# USB_UART.net
KiCad netlist of a schematic drawn in Altium Designer
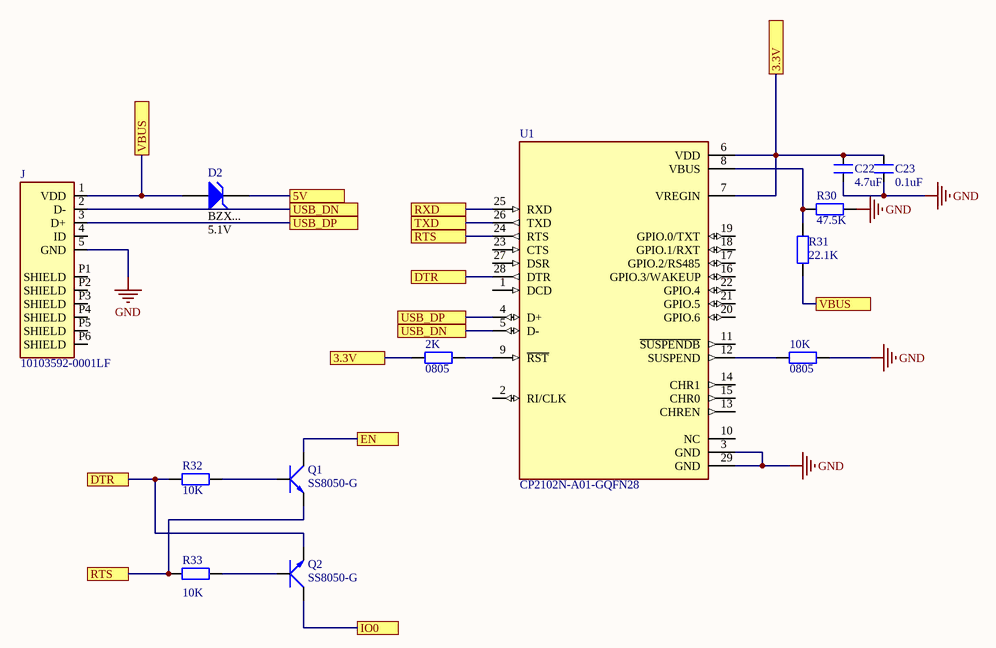
[diagram p0: USB_UART.SchDoc]

(export (version "E")
  (design (tool "Eeschema 10.0.6"))
  (components
    (comp (ref "2K")
      (value "0805")
      (footprint "DIEN TRO 0805")
      (description "RES_0805")
      (fields (field (name "Comment") "RES_SMD_0805") (field (name "PUBLISHER") "Altium Limited"))
      (libsource (lib "") (part "RES_SMD_0805_1"))
    )
    (comp (ref "10K")
      (value "0805")
      (footprint "DIEN TRO 0805")
      (description "RES_0805")
      (fields (field (name "Comment") "RES_SMD_0805") (field (name "PUBLISHER") "Altium Limited"))
      (libsource (lib "") (part "RES_SMD_0805_1"))
    )
    (comp (ref "C22")
      (value "4.7uF")
      (footprint "SM-0805")
      (description "Cap SMD")
      (libsource (lib "hphonglib") (part "CM"))
    )
    (comp (ref "C23")
      (value "0.1uF")
      (footprint "SM-0805")
      (description "Cap SMD")
      (libsource (lib "hphonglib") (part "CM"))
    )
    (comp (ref "D2")
      (value "BZX...")
      (footprint "D1208")
      (description "Zener Diode")
      (fields
        (field (name "VOLT") "5.1V")
        (field (name "Comment") "Diode Zener")
        (field (name "PUBLISHER") "Altium Limited")
      )
      (libsource (lib "hphonglib") (part "Diode Zener"))
    )
    (comp (ref "J")
      (value "10103592-0001LF")
      (footprint "AMPHENOL_10103592-0001LF")
      (description "USB - micro B USB 2.0 Receptacle Connector 5 Position Surface Mount, Right Angle; Through Hole")
      (fields (field (name "MF") "Amphenol ICC"))
      (libsource (lib "EMG_IoT_V2.0") (part "10103592-0001LF"))
    )
    (comp (ref "Q1")
      (value "SS8050-G")
      (footprint "SOT23B")
      (description "NPN 600mW, ECB")
      (libsource (lib "hphonglib") (part "C1815_1"))
    )
    (comp (ref "Q2")
      (value "SS8050-G")
      (footprint "SOT23B")
      (description "NPN 600mW, ECB")
      (libsource (lib "hphonglib") (part "C1815_1"))
    )
    (comp (ref "R30")
      (value "47.5K")
      (footprint "DIEN TRO 0805")
      (description "RES_0805")
      (fields (field (name "Comment") "RES_SMD_0805") (field (name "PUBLISHER") "Altium Limited"))
      (libsource (lib "") (part "RES_SMD_0805_1"))
    )
    (comp (ref "R31")
      (value "22.1K")
      (footprint "DIEN TRO 0805")
      (description "RES_0805")
      (fields (field (name "Comment") "RES_SMD_0805") (field (name "PUBLISHER") "Altium Limited"))
      (libsource (lib "hphonglib") (part "RES_SMD_0805"))
    )
    (comp (ref "R32")
      (value "10K")
      (footprint "DIEN TRO 0805")
      (description "RES_0805")
      (fields (field (name "Comment") "RES_SMD_0805") (field (name "PUBLISHER") "Altium Limited"))
      (libsource (lib "") (part "RES_SMD_0805_1"))
    )
    (comp (ref "R33")
      (value "10K")
      (footprint "DIEN TRO 0805")
      (description "RES_0805")
      (fields (field (name "Comment") "RES_SMD_0805") (field (name "PUBLISHER") "Altium Limited"))
      (libsource (lib "") (part "RES_SMD_0805_1"))
    )
    (comp (ref "U1")
      (value "CP2102N-A01-GQFN28")
      (footprint "QFN50P500X500X80-29N")
      (description "USB Bridge, USB to UART USB 2.0 UART Interface 28-QFN (5x5)")
      (fields (field (name "MF") "Silicon Labs"))
      (libsource (lib "EMG_IoT_V2.0") (part "CP2102N-A01-GQFN28"))
    )
  )
  (nets
    (net (code "1") (name "/3.3V") (class "Default")
      (node (ref "2K") (pin "1") (pinfunction "1_1") (pintype "passive"))
      (node (ref "C22") (pin "2") (pinfunction "2_2") (pintype "passive"))
      (node (ref "C23") (pin "2") (pinfunction "2_2") (pintype "passive"))
      (node (ref "U1") (pin "6") (pinfunction "VDD_6") (pintype "power_in"))
      (node (ref "U1") (pin "7") (pinfunction "VREGIN_7") (pintype "power_in"))
    )
    (net (code "2") (name "/5V") (class "Default")
      (node (ref "D2") (pin "2") (pinfunction "K_2") (pintype "passive"))
    )
    (net (code "3") (name "/DTR") (class "Default")
      (node (ref "Q2") (pin "1") (pinfunction "E_1") (pintype "passive"))
      (node (ref "R32") (pin "1") (pinfunction "1_1") (pintype "passive"))
      (node (ref "U1") (pin "28") (pinfunction "DTR_28") (pintype "output"))
    )
    (net (code "4") (name "/EN") (class "Default")
      (node (ref "Q1") (pin "2") (pinfunction "C_2") (pintype "passive"))
    )
    (net (code "5") (name "/IO0") (class "Default")
      (node (ref "Q2") (pin "2") (pinfunction "C_2") (pintype "passive"))
    )
    (net (code "6") (name "/RTS") (class "Default")
      (node (ref "Q1") (pin "1") (pinfunction "E_1") (pintype "passive"))
      (node (ref "R33") (pin "1") (pinfunction "1_1") (pintype "passive"))
      (node (ref "U1") (pin "24") (pinfunction "RTS_24") (pintype "output"))
    )
    (net (code "7") (name "/RXD") (class "Default")
      (node (ref "U1") (pin "25") (pinfunction "RXD_25") (pintype "input"))
    )
    (net (code "8") (name "/TXD") (class "Default")
      (node (ref "U1") (pin "26") (pinfunction "TXD_26") (pintype "output"))
    )
    (net (code "9") (name "/USB_DN") (class "Default")
      (node (ref "J") (pin "2") (pinfunction "D-_2") (pintype "bidirectional"))
      (node (ref "U1") (pin "5") (pinfunction "D-_5") (pintype "bidirectional"))
    )
    (net (code "10") (name "/USB_DP") (class "Default")
      (node (ref "J") (pin "3") (pinfunction "D+_3") (pintype "bidirectional"))
      (node (ref "U1") (pin "4") (pinfunction "D+_4") (pintype "bidirectional"))
    )
    (net (code "11") (name "/VBUS") (class "Default")
      (node (ref "D2") (pin "1") (pinfunction "A_1") (pintype "passive"))
      (node (ref "J") (pin "1") (pinfunction "VDD_1") (pintype "power_in"))
      (node (ref "R31") (pin "1") (pinfunction "1_1") (pintype "passive"))
    )
    (net (code "12") (name "GND") (class "Default")
      (node (ref "10K") (pin "2") (pinfunction "2_2") (pintype "passive"))
      (node (ref "C22") (pin "1") (pinfunction "1_1") (pintype "passive"))
      (node (ref "C23") (pin "1") (pinfunction "1_1") (pintype "passive"))
      (node (ref "J") (pin "5") (pinfunction "GND_5") (pintype "power_in"))
      (node (ref "R30") (pin "2") (pinfunction "2_2") (pintype "passive"))
      (node (ref "U1") (pin "29") (pinfunction "GND_29") (pintype "power_in"))
      (node (ref "U1") (pin "3") (pinfunction "GND_3") (pintype "power_in"))
    )
    (net (code "13") (name "Net-(Q1-B)") (class "Default")
      (node (ref "Q1") (pin "3") (pinfunction "B_3") (pintype "passive"))
      (node (ref "R32") (pin "2") (pinfunction "2_2") (pintype "passive"))
    )
    (net (code "14") (name "Net-(Q2-B)") (class "Default")
      (node (ref "Q2") (pin "3") (pinfunction "B_3") (pintype "passive"))
      (node (ref "R33") (pin "2") (pinfunction "2_2") (pintype "passive"))
    )
    (net (code "15") (name "Net-(U1-SUSPEND)") (class "Default")
      (node (ref "10K") (pin "1") (pinfunction "1_1") (pintype "passive"))
      (node (ref "U1") (pin "12") (pinfunction "SUSPEND_12") (pintype "output"))
    )
    (net (code "16") (name "Net-(U1-VBUS)") (class "Default")
      (node (ref "R30") (pin "1") (pinfunction "1_1") (pintype "passive"))
      (node (ref "R31") (pin "2") (pinfunction "2_2") (pintype "passive"))
      (node (ref "U1") (pin "8") (pinfunction "VBUS_8") (pintype "power_in"))
    )
    (net (code "17") (name "Net-(U1-~{RST})") (class "Default")
      (node (ref "2K") (pin "2") (pinfunction "2_2") (pintype "passive"))
      (node (ref "U1") (pin "9") (pinfunction "~{RST}_9") (pintype "input"))
    )
    (net (code "18") (name "unconnected-(J-ID-Pad4)") (class "Default")
      (node (ref "J") (pin "4") (pinfunction "ID_4") (pintype "bidirectional"))
    )
    (net (code "19") (name "unconnected-(J-SHIELD-PadP1)") (class "Default")
      (node (ref "J") (pin "P1") (pinfunction "SHIELD_P1") (pintype "power_in"))
    )
    (net (code "20") (name "unconnected-(J-SHIELD-PadP2)") (class "Default")
      (node (ref "J") (pin "P2") (pinfunction "SHIELD_P2") (pintype "power_in"))
    )
    (net (code "21") (name "unconnected-(J-SHIELD-PadP3)") (class "Default")
      (node (ref "J") (pin "P3") (pinfunction "SHIELD_P3") (pintype "power_in"))
    )
    (net (code "22") (name "unconnected-(J-SHIELD-PadP4)") (class "Default")
      (node (ref "J") (pin "P4") (pinfunction "SHIELD_P4") (pintype "power_in"))
    )
    (net (code "23") (name "unconnected-(J-SHIELD-PadP5)") (class "Default")
      (node (ref "J") (pin "P5") (pinfunction "SHIELD_P5") (pintype "power_in"))
    )
    (net (code "24") (name "unconnected-(J-SHIELD-PadP6)") (class "Default")
      (node (ref "J") (pin "P6") (pinfunction "SHIELD_P6") (pintype "power_in"))
    )
    (net (code "25") (name "unconnected-(U1-CHR0-Pad15)") (class "Default")
      (node (ref "U1") (pin "15") (pinfunction "CHR0_15") (pintype "output"))
    )
    (net (code "26") (name "unconnected-(U1-CHR1-Pad14)") (class "Default")
      (node (ref "U1") (pin "14") (pinfunction "CHR1_14") (pintype "output"))
    )
    (net (code "27") (name "unconnected-(U1-CHREN-Pad13)") (class "Default")
      (node (ref "U1") (pin "13") (pinfunction "CHREN_13") (pintype "output"))
    )
    (net (code "28") (name "unconnected-(U1-CTS-Pad23)") (class "Default")
      (node (ref "U1") (pin "23") (pinfunction "CTS_23") (pintype "input"))
    )
    (net (code "29") (name "unconnected-(U1-DCD-Pad1)") (class "Default")
      (node (ref "U1") (pin "1") (pinfunction "DCD_1") (pintype "input"))
    )
    (net (code "30") (name "unconnected-(U1-DSR-Pad27)") (class "Default")
      (node (ref "U1") (pin "27") (pinfunction "DSR_27") (pintype "input"))
    )
    (net (code "31") (name "unconnected-(U1-GPIO.0{slash}TXT-Pad19)") (class "Default")
      (node (ref "U1") (pin "19") (pinfunction "GPIO.0/TXT_19") (pintype "bidirectional"))
    )
    (net (code "32") (name "unconnected-(U1-GPIO.1{slash}RXT-Pad18)") (class "Default")
      (node (ref "U1") (pin "18") (pinfunction "GPIO.1/RXT_18") (pintype "bidirectional"))
    )
    (net (code "33") (name "unconnected-(U1-GPIO.2{slash}RS485-Pad17)") (class "Default")
      (node (ref "U1") (pin "17") (pinfunction "GPIO.2/RS485_17") (pintype "bidirectional"))
    )
    (net (code "34") (name "unconnected-(U1-GPIO.3{slash}WAKEUP-Pad16)") (class "Default")
      (node (ref "U1") (pin "16") (pinfunction "GPIO.3/WAKEUP_16") (pintype "bidirectional"))
    )
    (net (code "35") (name "unconnected-(U1-GPIO.4-Pad22)") (class "Default")
      (node (ref "U1") (pin "22") (pinfunction "GPIO.4_22") (pintype "bidirectional"))
    )
    (net (code "36") (name "unconnected-(U1-GPIO.5-Pad21)") (class "Default")
      (node (ref "U1") (pin "21") (pinfunction "GPIO.5_21") (pintype "bidirectional"))
    )
    (net (code "37") (name "unconnected-(U1-GPIO.6-Pad20)") (class "Default")
      (node (ref "U1") (pin "20") (pinfunction "GPIO.6_20") (pintype "bidirectional"))
    )
    (net (code "38") (name "unconnected-(U1-NC-Pad10)") (class "Default")
      (node (ref "U1") (pin "10") (pinfunction "NC_10") (pintype "passive"))
    )
    (net (code "39") (name "unconnected-(U1-RI{slash}CLK-Pad2)") (class "Default")
      (node (ref "U1") (pin "2") (pinfunction "RI/CLK_2") (pintype "bidirectional"))
    )
    (net (code "40") (name "unconnected-(U1-~{SUSPENDB}-Pad11)") (class "Default")
      (node (ref "U1") (pin "11") (pinfunction "~{SUSPENDB}_11") (pintype "output"))
    )
  )
)
